# backpower_main.net
KiCad netlist of a schematic drawn in Altium Designer
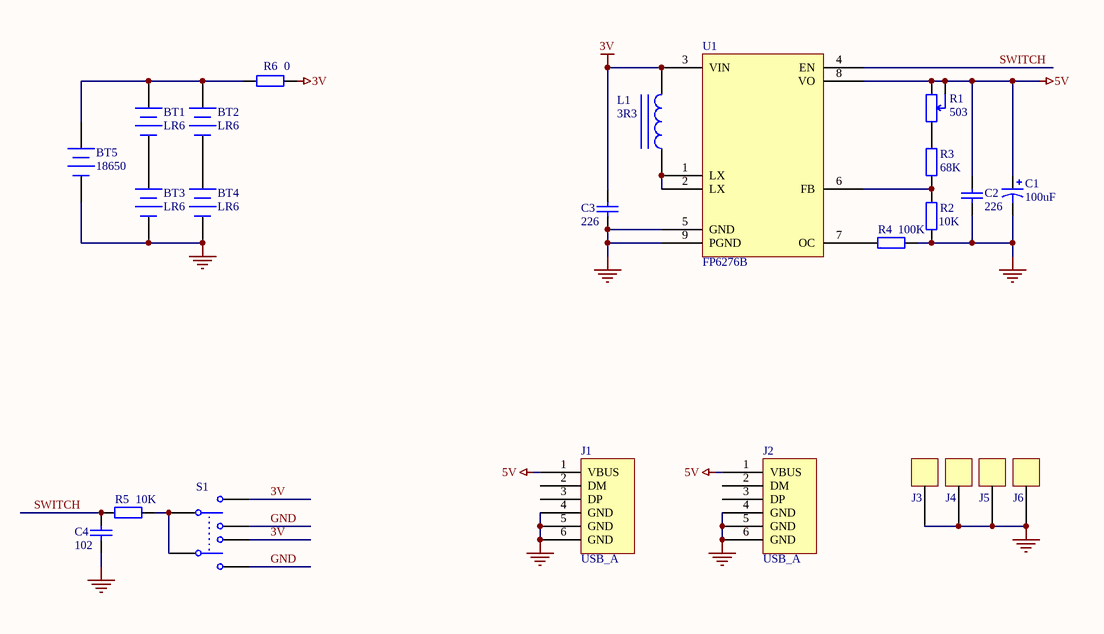
[diagram p0: backpower_main.SchDoc]

(export (version "E")
  (design (tool "Eeschema 10.0.6"))
  (components
    (comp (ref "BT1")
      (value "LR6")
      (footprint "Devices:BAT-LR6")
      (description "Multicell Battery")
      (fields (field (name "PUBLISHER") "Altium Limited"))
      (libsource (lib "Miscellaneous Devices") (part "Battery"))
    )
    (comp (ref "BT2")
      (value "LR6")
      (footprint "Devices:BAT-LR6")
      (description "Multicell Battery")
      (fields (field (name "PUBLISHER") "Altium Limited"))
      (libsource (lib "Miscellaneous Devices") (part "Battery"))
    )
    (comp (ref "BT3")
      (value "LR6")
      (footprint "Devices:BAT-LR6")
      (description "Multicell Battery")
      (fields (field (name "PUBLISHER") "Altium Limited"))
      (libsource (lib "Miscellaneous Devices") (part "Battery"))
    )
    (comp (ref "BT4")
      (value "LR6")
      (footprint "Devices:BAT-LR6")
      (description "Multicell Battery")
      (fields (field (name "PUBLISHER") "Altium Limited"))
      (libsource (lib "Miscellaneous Devices") (part "Battery"))
    )
    (comp (ref "BT5")
      (value "18650")
      (footprint "Devices:BAT-18650")
      (description "Multicell Battery")
      (fields (field (name "PUBLISHER") "Altium Limited"))
      (libsource (lib "Miscellaneous Devices") (part "Battery"))
    )
    (comp (ref "C1")
      (value "100uF")
      (footprint "Devices:CAP D6.3")
      (description "Polarized Capacitor (Radial)")
      (fields (field (name "PUBLISHER") "Altium Limited"))
      (libsource (lib "Miscellaneous Devices") (part "Cap Pol1"))
    )
    (comp (ref "C2")
      (value "226")
      (footprint "Devices:C5mm")
      (description "Capacitor")
      (fields (field (name "PUBLISHER") "Altium Limited"))
      (libsource (lib "Miscellaneous Devices") (part "Cap"))
    )
    (comp (ref "C3")
      (value "226")
      (footprint "Devices:C5mm")
      (description "Capacitor")
      (fields (field (name "PUBLISHER") "Altium Limited"))
      (libsource (lib "Miscellaneous Devices") (part "Cap"))
    )
    (comp (ref "C4")
      (value "102")
      (footprint "Devices:C5mm")
      (description "Capacitor")
      (fields (field (name "PUBLISHER") "Altium Limited"))
      (libsource (lib "Miscellaneous Devices") (part "Cap"))
    )
    (comp (ref "J1")
      (value "USB_A")
      (footprint "Devices:USB-A dip")
      (libsource (lib "Devices") (part "USB_A"))
    )
    (comp (ref "J2")
      (value "USB_A")
      (footprint "Devices:USB-A dip")
      (libsource (lib "Devices") (part "USB_A"))
    )
    (comp (ref "J3") (value "Hole") (footprint "Devices:PADR3/4") (libsource (lib "Devices") (part "Hole")))
    (comp (ref "J4") (value "Hole") (footprint "Devices:PADR3/4") (libsource (lib "Devices") (part "Hole")))
    (comp (ref "J5") (value "Hole") (footprint "Devices:PADR3/4") (libsource (lib "Devices") (part "Hole")))
    (comp (ref "J6") (value "Hole") (footprint "Devices:PADR3/4") (libsource (lib "Devices") (part "Hole")))
    (comp (ref "L1")
      (value "3R3")
      (footprint "Devices:CKPK0912")
      (description "Magnetic-Core Inductor")
      (fields (field (name "PUBLISHER") "Altium Limited"))
      (libsource (lib "Miscellaneous Devices") (part "Inductor Iron"))
    )
    (comp (ref "R1") (value "503") (footprint "Devices:VZ067") (libsource (lib "Devices") (part "Res Adj1")))
    (comp (ref "R2")
      (value "10K")
      (footprint "Devices:R1/4W")
      (description "Resistor")
      (fields (field (name "PUBLISHER") "Altium Limited"))
      (libsource (lib "") (part "Res2_1"))
    )
    (comp (ref "R3")
      (value "68K")
      (footprint "Devices:R1/4W")
      (description "Resistor")
      (fields (field (name "PUBLISHER") "Altium Limited"))
      (libsource (lib "") (part "Res2_1"))
    )
    (comp (ref "R4")
      (value "100K")
      (footprint "Devices:R1/4W")
      (description "Resistor")
      (fields (field (name "PUBLISHER") "Altium Limited"))
      (libsource (lib "Miscellaneous Devices") (part "Res2"))
    )
    (comp (ref "R5")
      (value "10K")
      (footprint "Devices:R1/4W")
      (description "Resistor")
      (fields (field (name "PUBLISHER") "Altium Limited"))
      (libsource (lib "") (part "Res2_2"))
    )
    (comp (ref "R6")
      (value "0")
      (footprint "Devices:R0603")
      (description "Resistor")
      (fields (field (name "PUBLISHER") "Altium Limited"))
      (libsource (lib "") (part "Res2_2"))
    )
    (comp (ref "S1")
      (value "SW-DPDT")
      (footprint "Devices:SW-8*8")
      (description "Double-Pole, Double-Throw Switch")
      (fields (field (name "PUBLISHER") "Altium Limited"))
      (libsource (lib "Miscellaneous Devices") (part "SW-DPDT"))
    )
    (comp (ref "U1")
      (value "FP6276B")
      (footprint "Devices:SOP8L_EP")
      (libsource (lib "Devices") (part "FP6276B"))
    )
  )
  (nets
    (net (code "1") (name "/SWITCH") (class "Default")
      (node (ref "C4") (pin "2") (pinfunction "2_2") (pintype "passive"))
      (node (ref "R5") (pin "1") (pinfunction "1_1") (pintype "passive"))
      (node (ref "U1") (pin "4") (pinfunction "EN_4") (pintype "passive"))
    )
    (net (code "2") (name "3V") (class "Default")
      (node (ref "C3") (pin "2") (pinfunction "2_2") (pintype "passive"))
      (node (ref "L1") (pin "2") (pinfunction "2_2") (pintype "passive"))
      (node (ref "R6") (pin "2") (pinfunction "2_2") (pintype "passive"))
      (node (ref "S1") (pin "2") (pinfunction "2_2") (pintype "passive"))
      (node (ref "S1") (pin "5") (pinfunction "5_5") (pintype "passive"))
      (node (ref "U1") (pin "3") (pinfunction "VIN_3") (pintype "passive"))
    )
    (net (code "3") (name "5V") (class "Default")
      (node (ref "C1") (pin "1") (pinfunction "1_1") (pintype "passive"))
      (node (ref "C2") (pin "1") (pinfunction "1_1") (pintype "passive"))
      (node (ref "J1") (pin "1") (pinfunction "VBUS_1") (pintype "passive"))
      (node (ref "J2") (pin "1") (pinfunction "VBUS_1") (pintype "passive"))
      (node (ref "R1") (pin "1") (pinfunction "1_1") (pintype "passive"))
      (node (ref "R1") (pin "2") (pinfunction "2_2") (pintype "passive"))
      (node (ref "U1") (pin "8") (pinfunction "VO_8") (pintype "passive"))
    )
    (net (code "4") (name "GND") (class "Default")
      (node (ref "BT3") (pin "2") (pinfunction "-_2") (pintype "passive"))
      (node (ref "BT4") (pin "2") (pinfunction "-_2") (pintype "passive"))
      (node (ref "BT5") (pin "2") (pinfunction "-_2") (pintype "passive"))
      (node (ref "C1") (pin "2") (pinfunction "2_2") (pintype "passive"))
      (node (ref "C2") (pin "2") (pinfunction "2_2") (pintype "passive"))
      (node (ref "C3") (pin "1") (pinfunction "1_1") (pintype "passive"))
      (node (ref "C4") (pin "1") (pinfunction "1_1") (pintype "passive"))
      (node (ref "J1") (pin "4") (pinfunction "GND_4") (pintype "passive"))
      (node (ref "J1") (pin "5") (pinfunction "GND_5") (pintype "passive"))
      (node (ref "J1") (pin "6") (pinfunction "GND_6") (pintype "passive"))
      (node (ref "J2") (pin "4") (pinfunction "GND_4") (pintype "passive"))
      (node (ref "J2") (pin "5") (pinfunction "GND_5") (pintype "passive"))
      (node (ref "J2") (pin "6") (pinfunction "GND_6") (pintype "passive"))
      (node (ref "J3") (pin "1") (pinfunction "1_1") (pintype "passive"))
      (node (ref "J4") (pin "1") (pinfunction "1_1") (pintype "passive"))
      (node (ref "J5") (pin "1") (pinfunction "1_1") (pintype "passive"))
      (node (ref "J6") (pin "1") (pinfunction "1_1") (pintype "passive"))
      (node (ref "R2") (pin "2") (pinfunction "2_2") (pintype "passive"))
      (node (ref "R4") (pin "1") (pinfunction "1_1") (pintype "passive"))
      (node (ref "S1") (pin "3") (pinfunction "3_3") (pintype "passive"))
      (node (ref "S1") (pin "6") (pinfunction "6_6") (pintype "passive"))
      (node (ref "U1") (pin "5") (pinfunction "GND_5") (pintype "passive"))
      (node (ref "U1") (pin "9") (pinfunction "PGND_9") (pintype "passive"))
    )
    (net (code "5") (name "Net-(BT1-+)") (class "Default")
      (node (ref "BT1") (pin "1") (pinfunction "+_1") (pintype "passive"))
      (node (ref "BT2") (pin "1") (pinfunction "+_1") (pintype "passive"))
      (node (ref "BT5") (pin "1") (pinfunction "+_1") (pintype "passive"))
      (node (ref "R6") (pin "1") (pinfunction "1_1") (pintype "passive"))
    )
    (net (code "6") (name "Net-(BT1--)") (class "Default")
      (node (ref "BT1") (pin "2") (pinfunction "-_2") (pintype "passive"))
      (node (ref "BT3") (pin "1") (pinfunction "+_1") (pintype "passive"))
    )
    (net (code "7") (name "Net-(BT2--)") (class "Default")
      (node (ref "BT2") (pin "2") (pinfunction "-_2") (pintype "passive"))
      (node (ref "BT4") (pin "1") (pinfunction "+_1") (pintype "passive"))
    )
    (net (code "8") (name "Net-(L1-Pad1)") (class "Default")
      (node (ref "L1") (pin "1") (pinfunction "1_1") (pintype "passive"))
      (node (ref "U1") (pin "1") (pinfunction "LX_1") (pintype "passive"))
      (node (ref "U1") (pin "2") (pinfunction "LX_2") (pintype "passive"))
    )
    (net (code "9") (name "Net-(R1-Pad3)") (class "Default")
      (node (ref "R1") (pin "3") (pinfunction "3_3") (pintype "passive"))
      (node (ref "R3") (pin "1") (pinfunction "1_1") (pintype "passive"))
    )
    (net (code "10") (name "Net-(R5-Pad2)") (class "Default")
      (node (ref "R5") (pin "2") (pinfunction "2_2") (pintype "passive"))
      (node (ref "S1") (pin "1") (pinfunction "1_1") (pintype "passive"))
      (node (ref "S1") (pin "4") (pinfunction "4_4") (pintype "passive"))
    )
    (net (code "11") (name "Net-(U1-FB)") (class "Default")
      (node (ref "R2") (pin "1") (pinfunction "1_1") (pintype "passive"))
      (node (ref "R3") (pin "2") (pinfunction "2_2") (pintype "passive"))
      (node (ref "U1") (pin "6") (pinfunction "FB_6") (pintype "passive"))
    )
    (net (code "12") (name "Net-(U1-OC)") (class "Default")
      (node (ref "R4") (pin "2") (pinfunction "2_2") (pintype "passive"))
      (node (ref "U1") (pin "7") (pinfunction "OC_7") (pintype "passive"))
    )
    (net (code "13") (name "unconnected-(J1-DM-Pad2)") (class "Default")
      (node (ref "J1") (pin "2") (pinfunction "DM_2") (pintype "passive"))
    )
    (net (code "14") (name "unconnected-(J1-DP-Pad3)") (class "Default")
      (node (ref "J1") (pin "3") (pinfunction "DP_3") (pintype "passive"))
    )
    (net (code "15") (name "unconnected-(J2-DM-Pad2)") (class "Default")
      (node (ref "J2") (pin "2") (pinfunction "DM_2") (pintype "passive"))
    )
    (net (code "16") (name "unconnected-(J2-DP-Pad3)") (class "Default")
      (node (ref "J2") (pin "3") (pinfunction "DP_3") (pintype "passive"))
    )
  )
)
